# Pressure_PM.net
KiCad netlist of a schematic drawn in Altium Designer
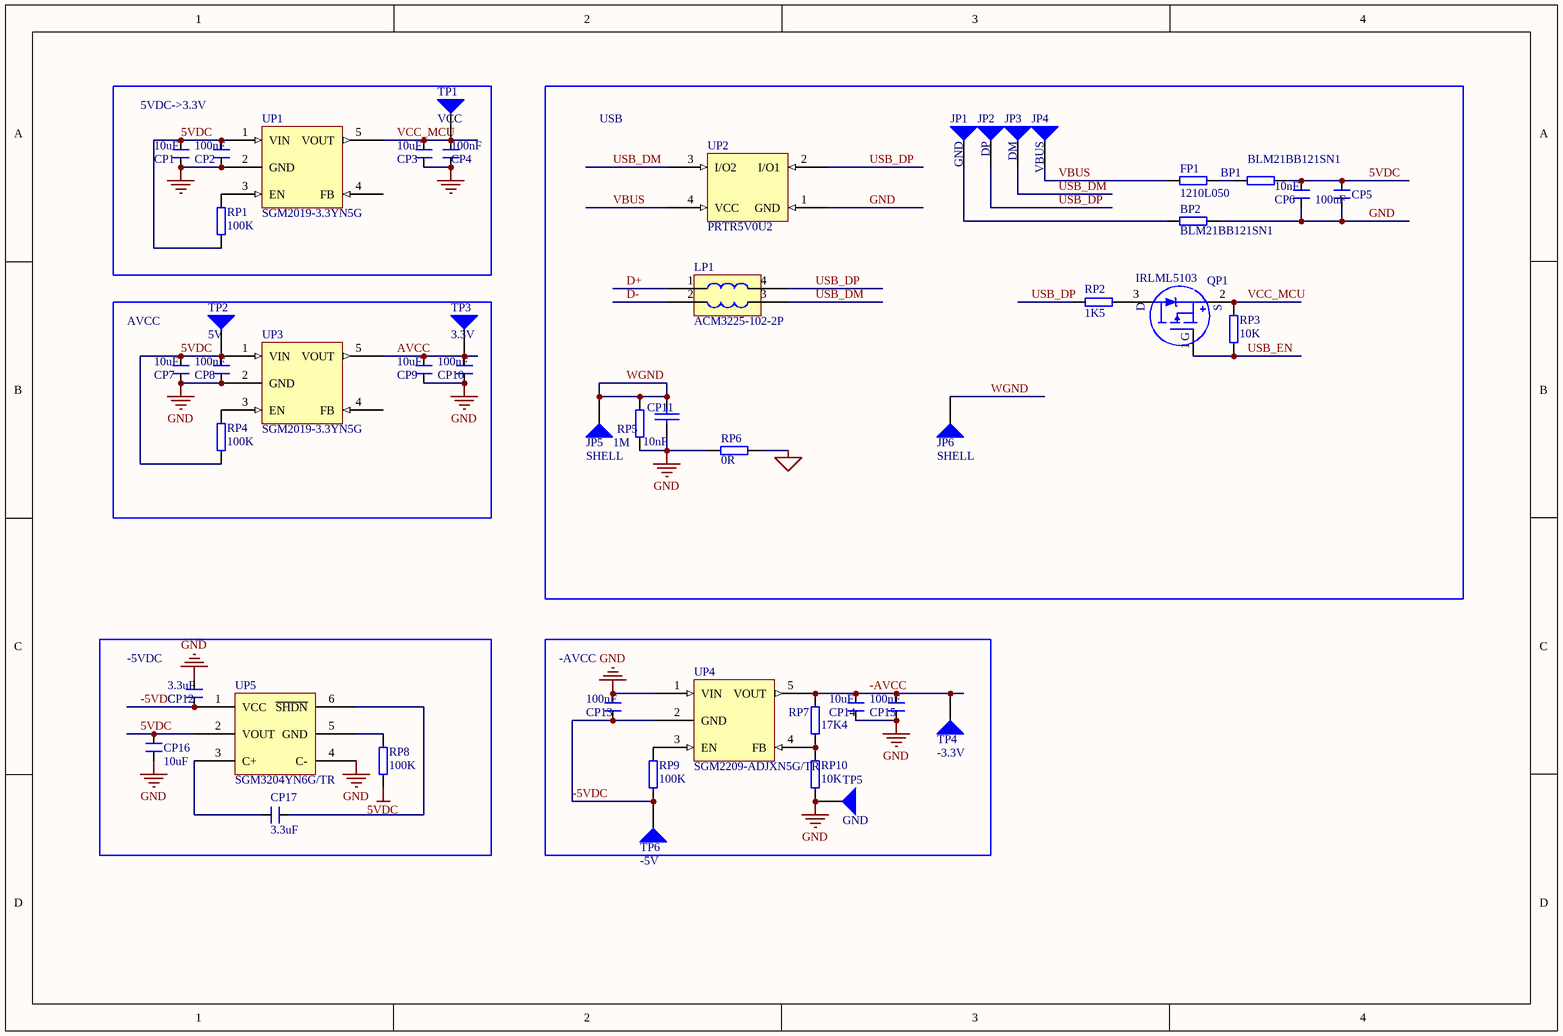
[diagram p0: Pressure_PM.SchDoc]

(export (version "E")
  (design (tool "Eeschema 10.0.6"))
  (components
    (comp (ref "BP1") (value "BLM21BB121SN1") (footprint "C0805") (libsource (lib "*") (part "RES")))
    (comp (ref "BP2") (value "BLM21BB121SN1") (footprint "C0805") (libsource (lib "*") (part "RES")))
    (comp (ref "CP1") (value "10uF") (footprint "C0805") (libsource (lib "*") (part "CAP_M")))
    (comp (ref "CP2") (value "100nF") (footprint "C0603_HSC100") (libsource (lib "*") (part "CAP_M")))
    (comp (ref "CP3") (value "10uF") (footprint "C0805") (libsource (lib "*") (part "CAP_M")))
    (comp (ref "CP4") (value "100nF") (footprint "C0603_HSC100") (libsource (lib "*") (part "CAP_M")))
    (comp (ref "CP5") (value "100uF") (footprint "c6032") (libsource (lib "*") (part "CAP_M")))
    (comp (ref "CP6") (value "10nF") (footprint "C0603_HSC100") (libsource (lib "*") (part "CAP_M")))
    (comp (ref "CP7") (value "10uF") (footprint "C0805") (libsource (lib "*") (part "CAP_M")))
    (comp (ref "CP8") (value "100nF") (footprint "C0603_HSC100") (libsource (lib "*") (part "CAP_M")))
    (comp (ref "CP9") (value "10uF") (footprint "C0805") (libsource (lib "*") (part "CAP_M")))
    (comp (ref "CP10") (value "100nF") (footprint "C0603_HSC100") (libsource (lib "*") (part "CAP_M")))
    (comp (ref "CP11")
      (value "10nF")
      (footprint "C0603_HSC100")
      (description "Capacitor")
      (libsource (lib "*") (part "CAP"))
    )
    (comp (ref "CP12") (value "3.3uF") (footprint "C0805") (libsource (lib "*") (part "CAP_M")))
    (comp (ref "CP13") (value "100nF") (footprint "C0603_HSC100") (libsource (lib "*") (part "CAP_M")))
    (comp (ref "CP14") (value "10uF") (footprint "C0805") (libsource (lib "*") (part "CAP_M")))
    (comp (ref "CP15") (value "100nF") (footprint "C0603_HSC100") (libsource (lib "*") (part "CAP_M")))
    (comp (ref "CP16") (value "10uF") (footprint "C0805") (libsource (lib "*") (part "CAP_M")))
    (comp (ref "CP17") (value "3.3uF") (footprint "C0805") (libsource (lib "*") (part "CAP_M")))
    (comp (ref "FP1") (value "1210L050") (footprint "C1206") (libsource (lib "*") (part "RES")))
    (comp (ref "JP1")
      (value "GND")
      (footprint "TPAD-CY")
      (description "Connector")
      (libsource (lib "MY_SCH") (part "TPAD"))
    )
    (comp (ref "JP2")
      (value "DP")
      (footprint "TPAD-CY")
      (description "Connector")
      (libsource (lib "MY_SCH") (part "TPAD"))
    )
    (comp (ref "JP3")
      (value "DM")
      (footprint "TPAD-CY")
      (description "Connector")
      (libsource (lib "MY_SCH") (part "TPAD"))
    )
    (comp (ref "JP4")
      (value "VBUS")
      (footprint "TPAD-CY")
      (description "Connector")
      (libsource (lib "MY_SCH") (part "TPAD"))
    )
    (comp (ref "JP5")
      (value "SHELL")
      (footprint "TPAD-CY")
      (description "Connector")
      (libsource (lib "MY_SCH") (part "TPAD"))
    )
    (comp (ref "JP6")
      (value "SHELL")
      (footprint "TPAD-HXS")
      (description "Connector")
      (libsource (lib "MY_SCH") (part "TPAD"))
    )
    (comp (ref "LP1")
      (value "ACM3225-102-2P")
      (footprint "3225")
      (description "ACM3225")
      (libsource (lib "*") (part "ACM3225-102-2P"))
    )
    (comp (ref "QP1") (value "IRLML5103") (footprint "TSMT3") (libsource (lib "*") (part "RTR030P02")))
    (comp (ref "RP1") (value "100K") (footprint "R0603_HSC100") (libsource (lib "*") (part "RES")))
    (comp (ref "RP2") (value "1K5") (footprint "R0603_HSC100") (libsource (lib "*") (part "RES")))
    (comp (ref "RP3") (value "10K") (footprint "R0603_HSC100") (libsource (lib "*") (part "RES")))
    (comp (ref "RP4") (value "100K") (footprint "R0603_HSC100") (libsource (lib "*") (part "RES")))
    (comp (ref "RP5") (value "1M") (footprint "R0603_HSC100") (libsource (lib "*") (part "RES")))
    (comp (ref "RP6") (value "0R") (footprint "R0603_HSC100") (libsource (lib "*") (part "RES")))
    (comp (ref "RP7") (value "17K4") (footprint "R0603_HSC100") (libsource (lib "*") (part "RES")))
    (comp (ref "RP8") (value "100K") (footprint "R0603_HSC100") (libsource (lib "*") (part "RES")))
    (comp (ref "RP9") (value "100K") (footprint "R0603_HSC100") (libsource (lib "*") (part "RES")))
    (comp (ref "RP10") (value "10K") (footprint "R0603_HSC100") (libsource (lib "*") (part "RES")))
    (comp (ref "TP1")
      (value "VCC")
      (footprint "TPAD-2MM")
      (description "Connector")
      (libsource (lib "MY_LIB") (part "TPAD"))
    )
    (comp (ref "TP2")
      (value "5V")
      (footprint "TPAD-2MM")
      (description "Connector")
      (libsource (lib "MY_LIB") (part "TPAD"))
    )
    (comp (ref "TP3")
      (value "3.3V")
      (footprint "TPAD-2MM")
      (description "Connector")
      (libsource (lib "MY_LIB") (part "TPAD"))
    )
    (comp (ref "TP4")
      (value "-3.3V")
      (footprint "TPAD-2MM")
      (description "Connector")
      (libsource (lib "MY_LIB") (part "TPAD"))
    )
    (comp (ref "TP5")
      (value "GND")
      (footprint "TPAD-2MM")
      (description "Connector")
      (libsource (lib "MY_LIB") (part "TPAD"))
    )
    (comp (ref "TP6")
      (value "-5V")
      (footprint "TPAD-2MM")
      (description "Connector")
      (libsource (lib "MY_LIB") (part "TPAD"))
    )
    (comp (ref "UP1")
      (value "SGM2019-3.3YN5G")
      (footprint "SOT23-5")
      (description "XC6201M331")
      (libsource (lib "MY_LIB") (part "XC6201"))
    )
    (comp (ref "UP2") (value "PRTR5V0U2") (footprint "SOT143B") (libsource (lib "*") (part "PRTR5V0U2")))
    (comp (ref "UP3")
      (value "SGM2019-3.3YN5G")
      (footprint "SOT23-5")
      (description "XC6201M331")
      (libsource (lib "MY_LIB") (part "XC6201"))
    )
    (comp (ref "UP4")
      (value "SGM2209-ADJXN5G/TR")
      (footprint "SOT23-5")
      (description "XC6201M331")
      (libsource (lib "MY_LIB") (part "XC6201"))
    )
    (comp (ref "UP5")
      (value "SGM3204YN6G/TR")
      (footprint "SOT23-6M")
      (libsource (lib "MY_SCH") (part "LTC1983"))
    )
  )
  (nets
    (net (code "1") (name "/-5VDC") (class "Default")
      (node (ref "CP12") (pin "1") (pintype "passive"))
      (node (ref "CP13") (pin "1") (pintype "passive"))
      (node (ref "RP9") (pin "2") (pintype "passive"))
      (node (ref "TP6") (pin "1") (pinfunction "1_1") (pintype "passive"))
      (node (ref "UP4") (pin "2") (pinfunction "GND_2") (pintype "power_in"))
      (node (ref "UP5") (pin "1") (pinfunction "VCC_1") (pintype "power_in"))
    )
    (net (code "2") (name "/-AVCC") (class "Default")
      (node (ref "CP14") (pin "2") (pintype "passive"))
      (node (ref "CP15") (pin "2") (pintype "passive"))
      (node (ref "RP7") (pin "1") (pintype "passive"))
      (node (ref "TP4") (pin "1") (pinfunction "1_1") (pintype "passive"))
      (node (ref "UP4") (pin "5") (pinfunction "VOUT_5") (pintype "output"))
    )
    (net (code "3") (name "/AVCC") (class "Default")
      (node (ref "CP10") (pin "2") (pintype "passive"))
      (node (ref "CP9") (pin "2") (pintype "passive"))
      (node (ref "TP3") (pin "1") (pinfunction "1_1") (pintype "passive"))
      (node (ref "UP3") (pin "5") (pinfunction "VOUT_5") (pintype "output"))
    )
    (net (code "4") (name "/D+") (class "Default")
      (node (ref "LP1") (pin "1") (pinfunction "1_1") (pintype "power_in"))
    )
    (net (code "5") (name "/D-") (class "Default")
      (node (ref "LP1") (pin "2") (pinfunction "2_2") (pintype "passive"))
    )
    (net (code "6") (name "/USB_DM") (class "Default")
      (node (ref "JP3") (pin "1") (pinfunction "1_1") (pintype "passive"))
      (node (ref "LP1") (pin "3") (pinfunction "3_3") (pintype "power_in"))
      (node (ref "UP2") (pin "3") (pinfunction "I/O2_3") (pintype "input"))
    )
    (net (code "7") (name "/USB_DP") (class "Default")
      (node (ref "JP2") (pin "1") (pinfunction "1_1") (pintype "passive"))
      (node (ref "LP1") (pin "4") (pinfunction "4_4") (pintype "passive"))
      (node (ref "RP2") (pin "2") (pintype "passive"))
      (node (ref "UP2") (pin "2") (pinfunction "I/O1_2") (pintype "input"))
    )
    (net (code "8") (name "/USB_EN") (class "Default")
      (node (ref "QP1") (pin "1") (pintype "passive"))
      (node (ref "RP3") (pin "2") (pintype "passive"))
    )
    (net (code "9") (name "/VBUS") (class "Default")
      (node (ref "FP1") (pin "2") (pintype "passive"))
      (node (ref "JP4") (pin "1") (pinfunction "1_1") (pintype "passive"))
      (node (ref "UP2") (pin "4") (pinfunction "VCC_4") (pintype "input"))
    )
    (net (code "10") (name "/VCC_MCU") (class "Default")
      (node (ref "CP3") (pin "2") (pintype "passive"))
      (node (ref "CP4") (pin "2") (pintype "passive"))
      (node (ref "QP1") (pin "2") (pintype "passive"))
      (node (ref "RP3") (pin "1") (pintype "passive"))
      (node (ref "TP1") (pin "1") (pinfunction "1_1") (pintype "passive"))
      (node (ref "UP1") (pin "5") (pinfunction "VOUT_5") (pintype "output"))
    )
    (net (code "11") (name "/WGND") (class "Default")
      (node (ref "CP11") (pin "1") (pinfunction "1_1") (pintype "passive"))
      (node (ref "JP5") (pin "1") (pinfunction "1_1") (pintype "passive"))
      (node (ref "JP6") (pin "1") (pinfunction "1_1") (pintype "passive"))
      (node (ref "RP5") (pin "2") (pintype "passive"))
    )
    (net (code "12") (name "5VDC") (class "Default")
      (node (ref "BP1") (pin "1") (pintype "passive"))
      (node (ref "CP1") (pin "2") (pintype "passive"))
      (node (ref "CP16") (pin "1") (pintype "passive"))
      (node (ref "CP2") (pin "2") (pintype "passive"))
      (node (ref "CP5") (pin "1") (pintype "passive"))
      (node (ref "CP6") (pin "2") (pintype "passive"))
      (node (ref "CP7") (pin "2") (pintype "passive"))
      (node (ref "CP8") (pin "2") (pintype "passive"))
      (node (ref "RP1") (pin "2") (pintype "passive"))
      (node (ref "RP4") (pin "2") (pintype "passive"))
      (node (ref "RP8") (pin "1") (pintype "passive"))
      (node (ref "TP2") (pin "1") (pinfunction "1_1") (pintype "passive"))
      (node (ref "UP1") (pin "1") (pinfunction "VIN_1") (pintype "input"))
      (node (ref "UP3") (pin "1") (pinfunction "VIN_1") (pintype "input"))
      (node (ref "UP5") (pin "2") (pinfunction "VOUT_2") (pintype "power_in"))
    )
    (net (code "13") (name "AGND") (class "Default") (node (ref "RP6") (pin "1") (pintype "passive")))
    (net (code "14") (name "GND") (class "Default")
      (node (ref "BP2") (pin "1") (pintype "passive"))
      (node (ref "CP1") (pin "1") (pintype "passive"))
      (node (ref "CP10") (pin "1") (pintype "passive"))
      (node (ref "CP11") (pin "2") (pinfunction "2_2") (pintype "passive"))
      (node (ref "CP12") (pin "2") (pintype "passive"))
      (node (ref "CP13") (pin "2") (pintype "passive"))
      (node (ref "CP14") (pin "1") (pintype "passive"))
      (node (ref "CP15") (pin "1") (pintype "passive"))
      (node (ref "CP16") (pin "2") (pintype "passive"))
      (node (ref "CP2") (pin "1") (pintype "passive"))
      (node (ref "CP3") (pin "1") (pintype "passive"))
      (node (ref "CP4") (pin "1") (pintype "passive"))
      (node (ref "CP5") (pin "2") (pintype "passive"))
      (node (ref "CP6") (pin "1") (pintype "passive"))
      (node (ref "CP7") (pin "1") (pintype "passive"))
      (node (ref "CP8") (pin "1") (pintype "passive"))
      (node (ref "CP9") (pin "1") (pintype "passive"))
      (node (ref "RP10") (pin "2") (pintype "passive"))
      (node (ref "RP5") (pin "1") (pintype "passive"))
      (node (ref "RP6") (pin "2") (pintype "passive"))
      (node (ref "TP5") (pin "1") (pinfunction "1_1") (pintype "passive"))
      (node (ref "UP1") (pin "2") (pinfunction "GND_2") (pintype "power_in"))
      (node (ref "UP2") (pin "1") (pinfunction "GND_1") (pintype "input"))
      (node (ref "UP3") (pin "2") (pinfunction "GND_2") (pintype "power_in"))
      (node (ref "UP4") (pin "1") (pinfunction "VIN_1") (pintype "input"))
      (node (ref "UP5") (pin "4") (pinfunction "C-_4") (pintype "power_in"))
    )
    (net (code "15") (name "Net-(BP1-Pad2)") (class "Default")
      (node (ref "BP1") (pin "2") (pintype "passive"))
      (node (ref "FP1") (pin "1") (pintype "passive"))
    )
    (net (code "16") (name "Net-(BP2-Pad2)") (class "Default")
      (node (ref "BP2") (pin "2") (pintype "passive"))
      (node (ref "JP1") (pin "1") (pinfunction "1_1") (pintype "passive"))
    )
    (net (code "17") (name "Net-(QP1-Pad3)") (class "Default")
      (node (ref "QP1") (pin "3") (pintype "passive"))
      (node (ref "RP2") (pin "1") (pintype "passive"))
    )
    (net (code "18") (name "Net-(UP1-EN)") (class "Default")
      (node (ref "RP1") (pin "1") (pintype "passive"))
      (node (ref "UP1") (pin "3") (pinfunction "EN_3") (pintype "input"))
    )
    (net (code "19") (name "Net-(UP3-EN)") (class "Default")
      (node (ref "RP4") (pin "1") (pintype "passive"))
      (node (ref "UP3") (pin "3") (pinfunction "EN_3") (pintype "input"))
    )
    (net (code "20") (name "Net-(UP4-EN)") (class "Default")
      (node (ref "RP9") (pin "1") (pintype "passive"))
      (node (ref "UP4") (pin "3") (pinfunction "EN_3") (pintype "input"))
    )
    (net (code "21") (name "Net-(UP4-FB)") (class "Default")
      (node (ref "RP10") (pin "1") (pintype "passive"))
      (node (ref "RP7") (pin "2") (pintype "passive"))
      (node (ref "UP4") (pin "4") (pinfunction "FB_4") (pintype "input"))
    )
    (net (code "22") (name "Net-(UP5-C+)") (class "Default")
      (node (ref "CP17") (pin "2") (pintype "passive"))
      (node (ref "UP5") (pin "3") (pinfunction "C+_3") (pintype "power_in"))
    )
    (net (code "23") (name "Net-(UP5-GND)") (class "Default")
      (node (ref "RP8") (pin "2") (pintype "passive"))
      (node (ref "UP5") (pin "5") (pinfunction "GND_5") (pintype "power_in"))
    )
    (net (code "24") (name "Net-(UP5-~{SHDN})") (class "Default")
      (node (ref "CP17") (pin "1") (pintype "passive"))
      (node (ref "UP5") (pin "6") (pinfunction "~{SHDN}_6") (pintype "power_in"))
    )
    (net (code "25") (name "unconnected-(UP1-FB-Pad4)") (class "Default")
      (node (ref "UP1") (pin "4") (pinfunction "FB_4") (pintype "input"))
    )
    (net (code "26") (name "unconnected-(UP3-FB-Pad4)") (class "Default")
      (node (ref "UP3") (pin "4") (pinfunction "FB_4") (pintype "input"))
    )
  )
)
